# LDO_4V3.net
KiCad netlist of a schematic drawn in Altium Designer
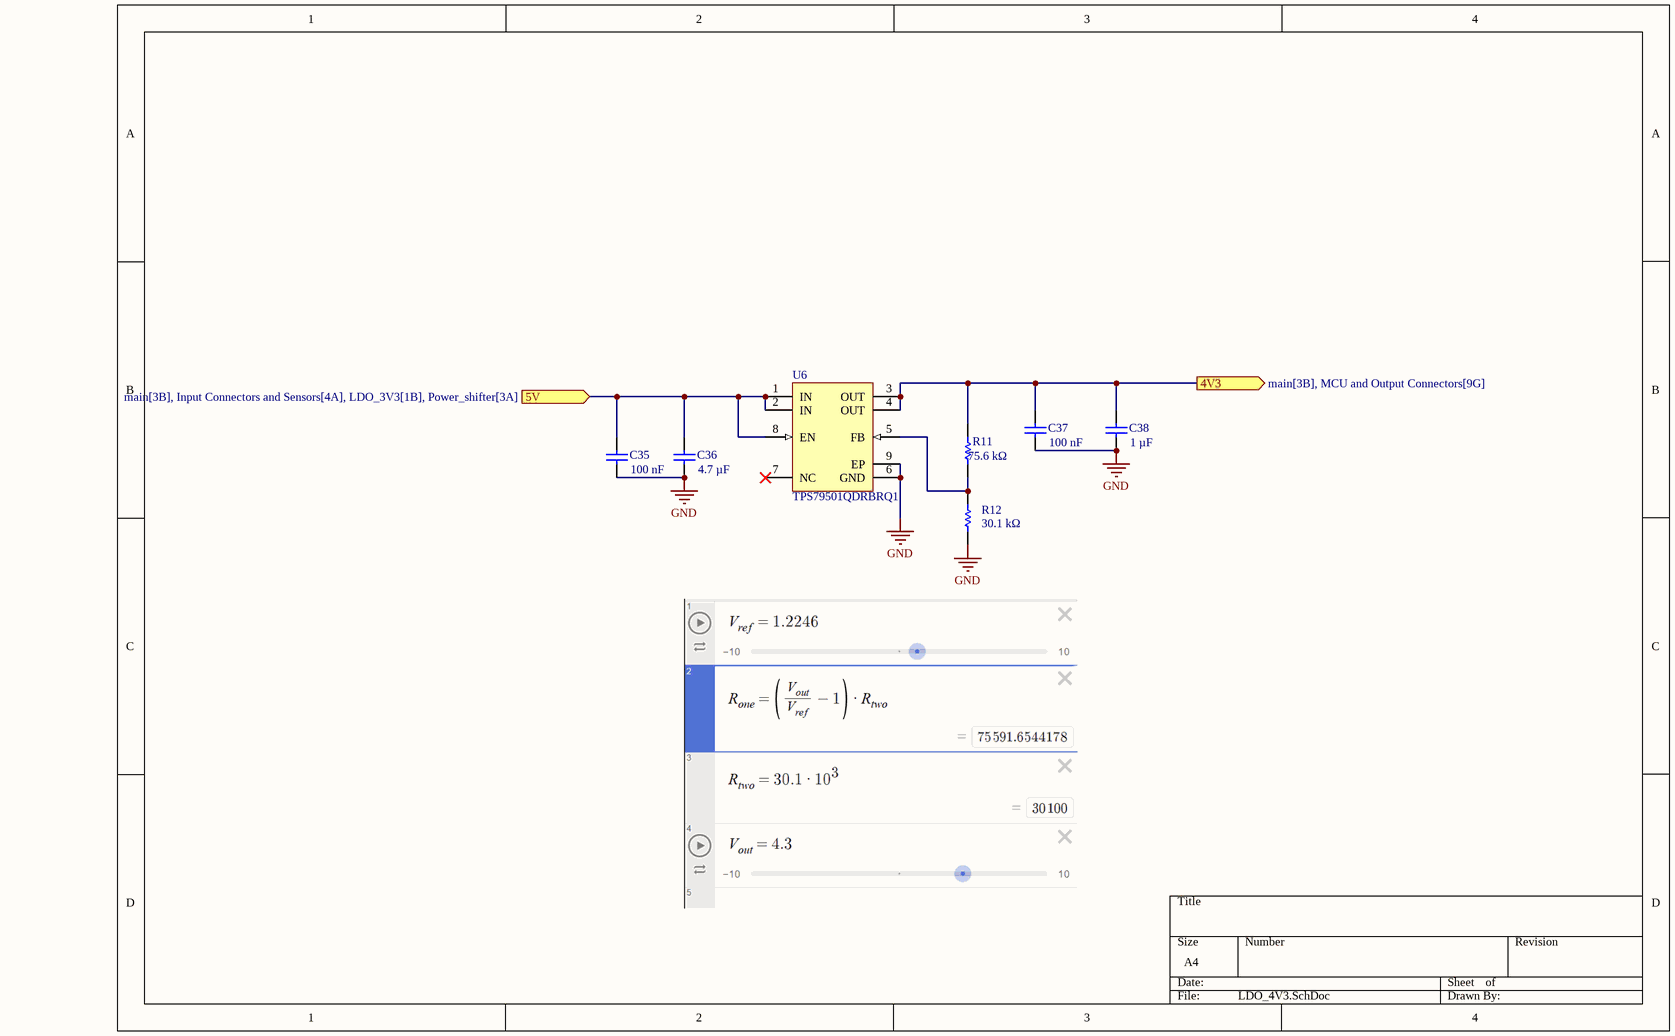
[diagram p0: LDO_4V3.SchDoc]

(export (version "E")
  (design (tool "Eeschema 10.0.6"))
  (components
    (comp (ref "C35")
      (value "100 nF")
      (footprint "0402_CAPC1005L")
      (description "Capacitor (Semiconductor SIM Model)")
      (fields (field (name "Comment") "Cap Semi") (field (name "PUBLISHER") "Altium Limited"))
      (libsource (lib "MiscDev 3") (part "Cap Semi"))
    )
    (comp (ref "C36")
      (value "4.7 µF")
      (footprint "0805_CAPC2012L")
      (description "Capacitor (Semiconductor SIM Model)")
      (fields (field (name "Comment") "Cap Semi") (field (name "PUBLISHER") "Altium Limited"))
      (libsource (lib "MiscDev 3") (part "Cap Semi"))
    )
    (comp (ref "C37")
      (value "100 nF")
      (footprint "0402_CAPC1005L")
      (description "Capacitor (Semiconductor SIM Model)")
      (fields (field (name "Comment") "Cap Semi") (field (name "PUBLISHER") "Altium Limited"))
      (libsource (lib "MiscDev 3") (part "Cap Semi"))
    )
    (comp (ref "C38")
      (value "1 µF")
      (footprint "0805_CAPC2012L")
      (description "Capacitor (Semiconductor SIM Model)")
      (fields (field (name "Comment") "Cap Semi") (field (name "PUBLISHER") "Altium Limited"))
      (libsource (lib "MiscDev 3") (part "Cap Semi"))
    )
    (comp (ref "R11")
      (value "75.6 kΩ")
      (footprint "0402_RESC1005L")
      (description "Semiconductor Resistor")
      (fields (field (name "Comment") "Res Semi") (field (name "PUBLISHER") "Altium Limited"))
      (libsource (lib "MiscDev 3") (part "Res Semi"))
    )
    (comp (ref "R12")
      (value "30.1 kΩ")
      (footprint "0402_RESC1005L")
      (description "Semiconductor Resistor")
      (fields (field (name "Comment") "Res Semi") (field (name "PUBLISHER") "Altium Limited"))
      (libsource (lib "MiscDev 3") (part "Res Semi"))
    )
    (comp (ref "U6")
      (value "TPS79501QDRBRQ1")
      (footprint "DRB0008B_V")
      (fields (field (name "MANUFACTURER") "Texas Instruments"))
      (libsource (lib "Altium Content Vault") (part "TI-TPS79501DRB8_A-2400X1650TP"))
    )
  )
  (nets
    (net (code "1") (name "/4V3") (class "Default")
      (node (ref "C37") (pin "2") (pinfunction "2_2") (pintype "passive"))
      (node (ref "C38") (pin "2") (pinfunction "2_2") (pintype "passive"))
      (node (ref "R11") (pin "2") (pinfunction "2_2") (pintype "passive"))
      (node (ref "U6") (pin "3") (pinfunction "OUT_3") (pintype "power_in"))
      (node (ref "U6") (pin "4") (pinfunction "OUT_4") (pintype "power_in"))
    )
    (net (code "2") (name "/5V") (class "Default")
      (node (ref "C35") (pin "2") (pinfunction "2_2") (pintype "passive"))
      (node (ref "C36") (pin "2") (pinfunction "2_2") (pintype "passive"))
      (node (ref "U6") (pin "1") (pinfunction "IN_1") (pintype "power_in"))
      (node (ref "U6") (pin "2") (pinfunction "IN_2") (pintype "power_in"))
      (node (ref "U6") (pin "8") (pinfunction "EN_8") (pintype "input"))
    )
    (net (code "3") (name "GND") (class "Default")
      (node (ref "C35") (pin "1") (pinfunction "1_1") (pintype "passive"))
      (node (ref "C36") (pin "1") (pinfunction "1_1") (pintype "passive"))
      (node (ref "C37") (pin "1") (pinfunction "1_1") (pintype "passive"))
      (node (ref "C38") (pin "1") (pinfunction "1_1") (pintype "passive"))
      (node (ref "R12") (pin "1") (pinfunction "1_1") (pintype "passive"))
      (node (ref "U6") (pin "6") (pinfunction "GND_6") (pintype "power_in"))
      (node (ref "U6") (pin "9") (pinfunction "EP_9") (pintype "passive"))
    )
    (net (code "4") (name "Net-(U6-FB)") (class "Default")
      (node (ref "R11") (pin "1") (pinfunction "1_1") (pintype "passive"))
      (node (ref "R12") (pin "2") (pinfunction "2_2") (pintype "passive"))
      (node (ref "U6") (pin "5") (pinfunction "FB_5") (pintype "input"))
    )
    (net (code "5") (name "unconnected-(U6-NC-Pad7)") (class "Default")
      (node (ref "U6") (pin "7") (pinfunction "NC_7") (pintype "passive+no_connect"))
    )
  )
)
